# USB_Boost.net
KiCad netlist of a schematic drawn in EAGLE
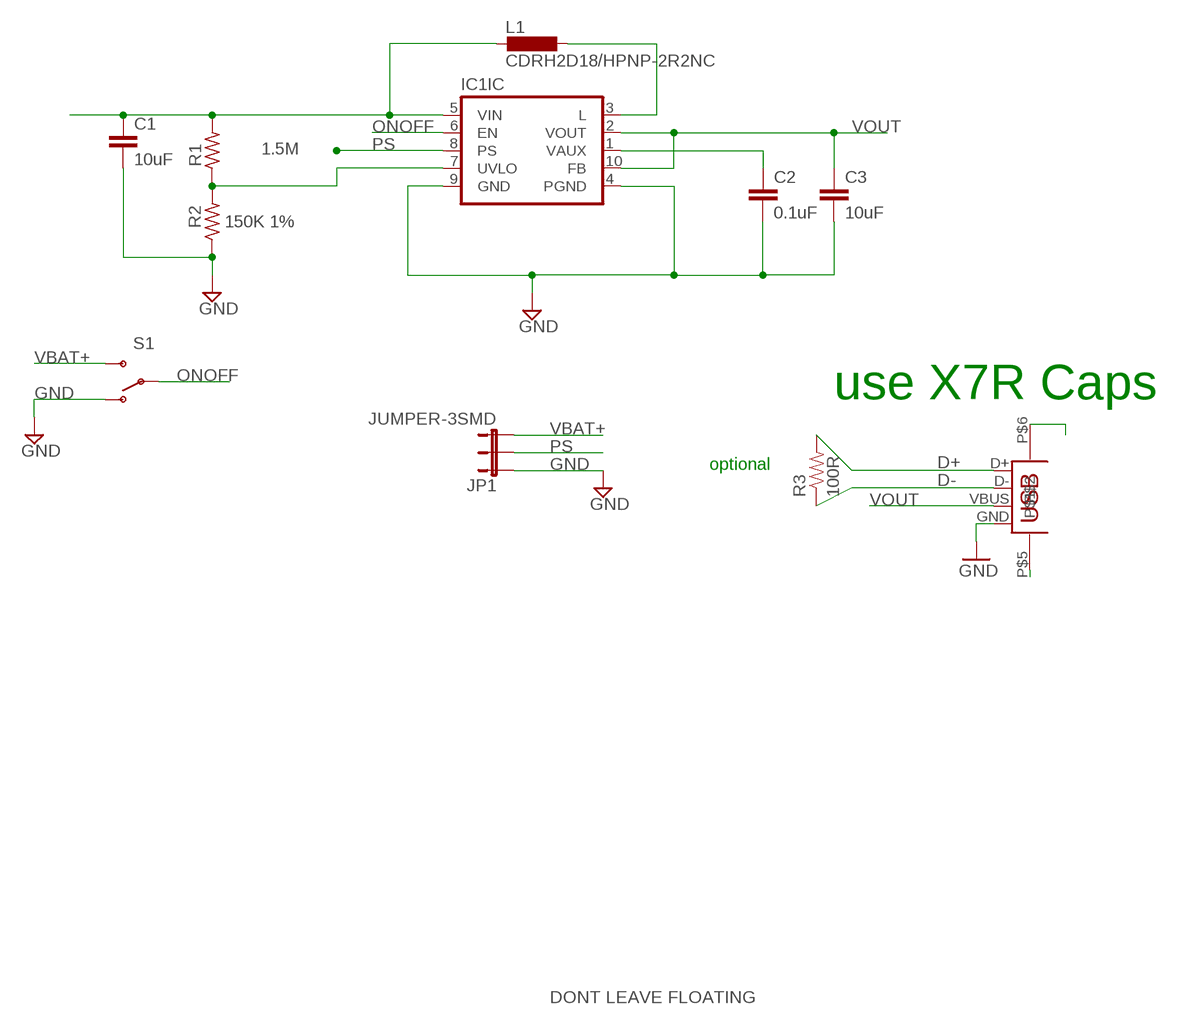
[diagram p0: schematic, sheet 1]
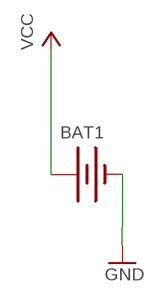
[diagram p1: schematic, sheet 2]

(export (version "E")
  (design (tool "Eeschema 10.0.6"))
  (components
    (comp (ref "C1")
      (value "10uF")
      (footprint "eagle-import:SPARKFUN_0603-CAP")
      (libsource (lib "eagle-import") (part "SPARKFUN_CAP0603-CAP"))
    )
    (comp (ref "C2")
      (value "0.1uF")
      (footprint "eagle-import:SPARKFUN_0603-CAP")
      (fields (field (name "MPN") "02016D104KAT2A"))
      (libsource (lib "eagle-import") (part "SPARKFUN_CAP0603-CAP"))
    )
    (comp (ref "C3")
      (value "10uF")
      (footprint "eagle-import:SPARKFUN_0603-CAP")
      (libsource (lib "eagle-import") (part "SPARKFUN_CAP0603-CAP"))
    )
    (comp (ref "IC1")
      (value "IC_TPS6120XQFN10")
      (footprint "eagle-import:QFN-10")
      (fields (field (name "PARTNO") "TPS61202DRCT"))
      (libsource (lib "eagle-import") (part "IC_TPS6120XQFN10"))
    )
    (comp (ref "JP1")
      (value "JUMPER-3SMD")
      (footprint "eagle-import:SJ_3")
      (libsource (lib "eagle-import") (part "JUMPER-3SMD"))
    )
    (comp (ref "L1")
      (value "CDRH2D18/HPNP-2R2NC")
      (footprint "eagle-import:CDRH2D18")
      (libsource (lib "eagle-import") (part "CDRH2D18"))
    )
    (comp (ref "R1")
      (value "1.5M")
      (footprint "eagle-import:RLC_0603")
      (fields (field (name "TOLERANCE") "5%"))
      (libsource (lib "eagle-import") (part "RESISTORRLC_0603"))
    )
    (comp (ref "R2")
      (value "150K 1%")
      (footprint "eagle-import:RLC_0603")
      (fields (field (name "TOLERANCE") "1%"))
      (libsource (lib "eagle-import") (part "RESISTORRLC_0603"))
    )
    (comp (ref "R3")
      (value "100R")
      (footprint "eagle-import:0805")
      (libsource (lib "eagle-import") (part "RESISTOR0805-RES"))
    )
    (comp (ref "S1")
      (value "SWITCH-SPDT-SMD-A")
      (footprint "eagle-import:SWITCH-SPST-SMD-A")
      (libsource (lib "eagle-import") (part "SWITCH-SPDT-SMD-A"))
    )
    (comp (ref "X1")
      (value "USBKUSBX-SMT-AS1N")
      (footprint "eagle-import:KSUBX-SMT-AS1N")
      (libsource (lib "eagle-import") (part "USBKUSBX-SMT-AS1N"))
    )
    (comp (ref "BAT1")
      (value "BATTERYCR123A")
      (footprint "eagle-import:BATTERY_CR123A")
      (libsource (lib "eagle-import") (part "BATTERYCR123A"))
    )
  )
  (nets
    (net (code "1") (name "D+") (class "Default")
      (node (ref "R3") (pin "2") (pinfunction "2_2") (pintype "passive"))
      (node (ref "X1") (pin "D+") (pinfunction "D+_D+") (pintype "bidirectional"))
    )
    (net (code "2") (name "D-") (class "Default")
      (node (ref "R3") (pin "1") (pinfunction "1_1") (pintype "passive"))
      (node (ref "X1") (pin "D-") (pinfunction "D-_D-") (pintype "bidirectional"))
    )
    (net (code "3") (name "GND") (class "Default")
      (node (ref "BAT1") (pin "-") (pinfunction "-_-") (pintype "power_in"))
      (node (ref "C1") (pin "2") (pinfunction "2_2") (pintype "passive"))
      (node (ref "C2") (pin "2") (pinfunction "2_2") (pintype "passive"))
      (node (ref "C3") (pin "2") (pinfunction "2_2") (pintype "passive"))
      (node (ref "IC1") (pin "4") (pinfunction "PGND_4") (pintype "power_in"))
      (node (ref "IC1") (pin "9") (pinfunction "GND_9") (pintype "power_in"))
      (node (ref "JP1") (pin "1") (pinfunction "1_1") (pintype "passive"))
      (node (ref "R2") (pin "1") (pinfunction "1_1") (pintype "passive"))
      (node (ref "S1") (pin "1") (pinfunction "O_1") (pintype "passive"))
      (node (ref "X1") (pin "GND") (pinfunction "GND_GND") (pintype "bidirectional"))
    )
    (net (code "4") (name "GNDUSB") (class "Default")
      (node (ref "X1") (pin "P$5") (pinfunction "P$1_P$5") (pintype "bidirectional"))
      (node (ref "X1") (pin "P$6") (pinfunction "P$2_P$6") (pintype "bidirectional"))
    )
    (net (code "5") (name "Net-(IC1B-L)") (class "Default")
      (node (ref "IC1") (pin "3") (pinfunction "L_3") (pintype "input"))
      (node (ref "L1") (pin "P$2") (pinfunction "2_P$2") (pintype "passive"))
    )
    (net (code "6") (name "Net-(IC1B-UVLO)") (class "Default")
      (node (ref "IC1") (pin "7") (pinfunction "UVLO_7") (pintype "input"))
      (node (ref "R1") (pin "1") (pinfunction "1_1") (pintype "passive"))
      (node (ref "R2") (pin "2") (pinfunction "2_2") (pintype "passive"))
    )
    (net (code "7") (name "Net-(IC1B-VAUX)") (class "Default")
      (node (ref "C2") (pin "1") (pinfunction "1_1") (pintype "passive"))
      (node (ref "IC1") (pin "1") (pinfunction "VAUX_1") (pintype "bidirectional"))
    )
    (net (code "8") (name "ONOFF") (class "Default")
      (node (ref "IC1") (pin "6") (pinfunction "EN_6") (pintype "input"))
      (node (ref "S1") (pin "2") (pinfunction "P_2") (pintype "passive"))
    )
    (net (code "9") (name "PS") (class "Default")
      (node (ref "IC1") (pin "8") (pinfunction "PS_8") (pintype "input"))
      (node (ref "JP1") (pin "2") (pinfunction "2_2") (pintype "passive"))
    )
    (net (code "10") (name "VBAT+") (class "Default")
      (node (ref "C1") (pin "1") (pinfunction "1_1") (pintype "passive"))
      (node (ref "IC1") (pin "5") (pinfunction "VIN_5") (pintype "input"))
      (node (ref "JP1") (pin "3") (pinfunction "3_3") (pintype "passive"))
      (node (ref "L1") (pin "P$1") (pinfunction "1_P$1") (pintype "passive"))
      (node (ref "R1") (pin "2") (pinfunction "2_2") (pintype "passive"))
      (node (ref "S1") (pin "3") (pinfunction "S_3") (pintype "passive"))
    )
    (net (code "11") (name "VCC") (class "Default")
      (node (ref "BAT1") (pin "+") (pinfunction "+_+") (pintype "power_in"))
    )
    (net (code "12") (name "VOUT") (class "Default")
      (node (ref "C3") (pin "1") (pinfunction "1_1") (pintype "passive"))
      (node (ref "IC1") (pin "10") (pinfunction "FB_10") (pintype "input"))
      (node (ref "IC1") (pin "2") (pinfunction "VOUT_2") (pintype "output"))
      (node (ref "X1") (pin "VBUS") (pinfunction "VBUS_VBUS") (pintype "bidirectional"))
    )
  )
)
